# rigidPCB2_rev.net
KiCad netlist of a schematic drawn in Altium Designer
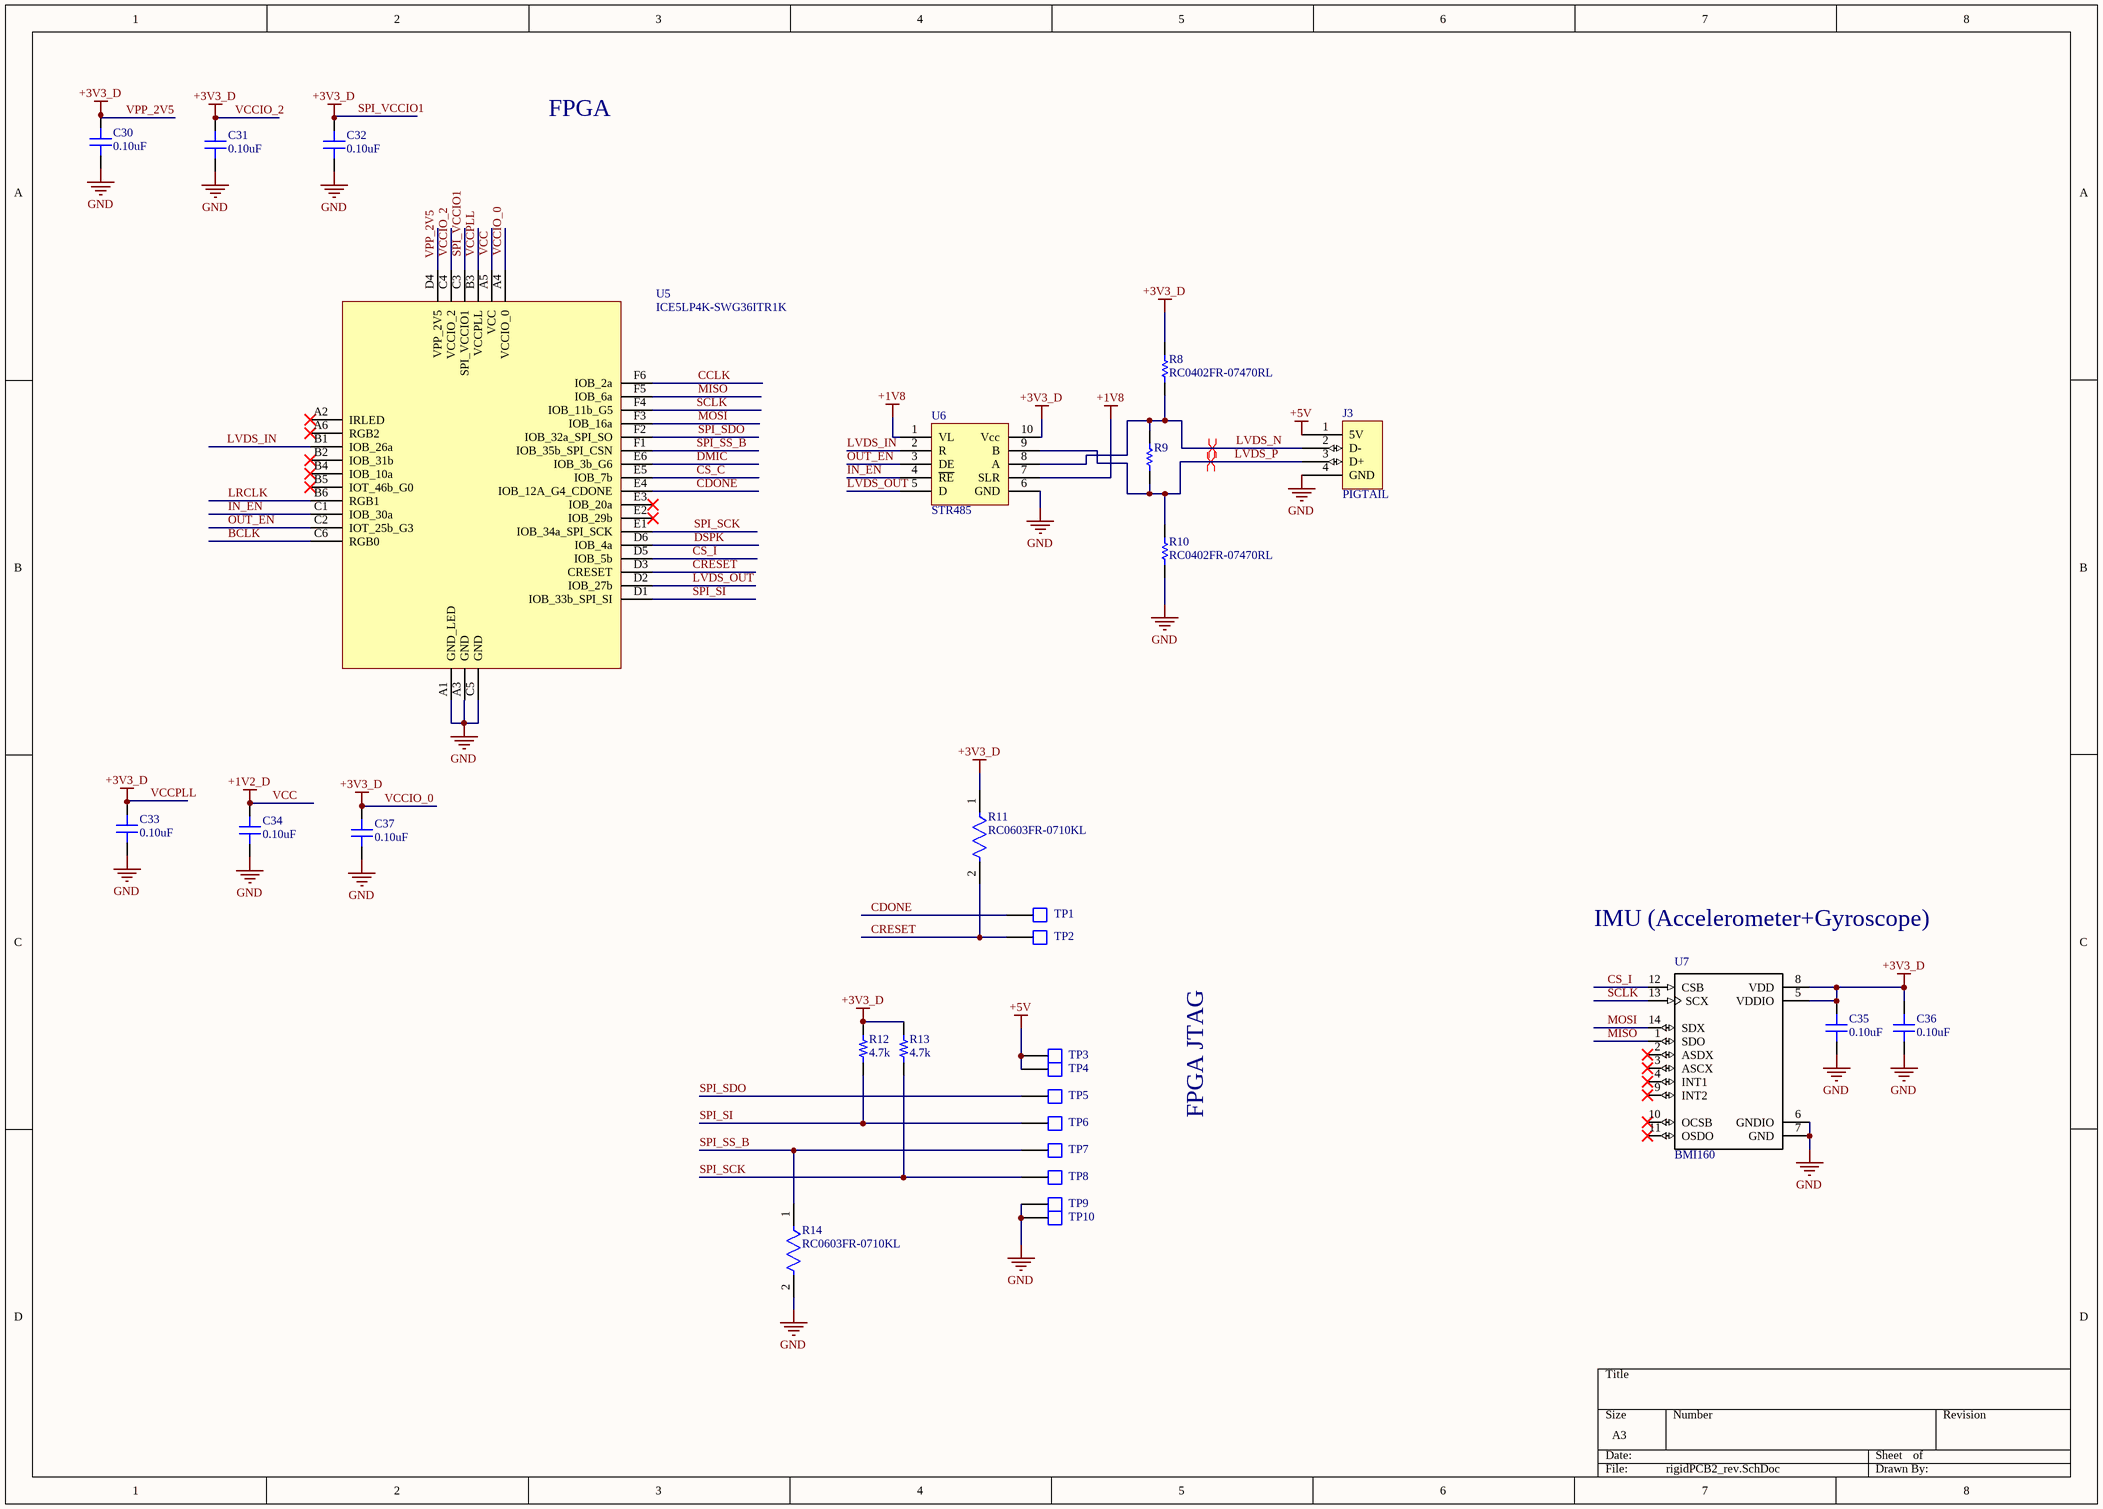
[diagram p0: rigidPCB2_rev.SchDoc]

(export (version "E")
  (design (tool "Eeschema 10.0.6"))
  (components
    (comp (ref "C30")
      (value "0.10uF")
      (footprint "CAP 0201/0603")
      (description "CAP CER 0.1UF 10V X5R 0201")
      (fields
        (field (name "PART NUMBER") "CL03A104KP3NNNC")
        (field (name "MANUFACTURER") "Samsung Electro-Mechanics America, Inc.")
      )
      (libsource (lib "Celestial Library Database") (part "Capacitor"))
    )
    (comp (ref "C31")
      (value "0.10uF")
      (footprint "CAP 0201/0603")
      (description "CAP CER 0.1UF 10V X5R 0201")
      (fields
        (field (name "PART NUMBER") "CL03A104KP3NNNC")
        (field (name "MANUFACTURER") "Samsung Electro-Mechanics America, Inc.")
      )
      (libsource (lib "Celestial Library Database") (part "Capacitor"))
    )
    (comp (ref "C32")
      (value "0.10uF")
      (footprint "CAP 0201/0603")
      (description "CAP CER 0.1UF 10V X5R 0201")
      (fields
        (field (name "PART NUMBER") "CL03A104KP3NNNC")
        (field (name "MANUFACTURER") "Samsung Electro-Mechanics America, Inc.")
      )
      (libsource (lib "Celestial Library Database") (part "Capacitor"))
    )
    (comp (ref "C33")
      (value "0.10uF")
      (footprint "CAP 0201/0603")
      (description "CAP CER 0.1UF 10V X5R 0201")
      (fields
        (field (name "PART NUMBER") "CL03A104KP3NNNC")
        (field (name "MANUFACTURER") "Samsung Electro-Mechanics America, Inc.")
      )
      (libsource (lib "Celestial Library Database") (part "Capacitor"))
    )
    (comp (ref "C34")
      (value "0.10uF")
      (footprint "CAP 0201/0603")
      (description "CAP CER 0.1UF 10V X5R 0201")
      (fields
        (field (name "PART NUMBER") "CL03A104KP3NNNC")
        (field (name "MANUFACTURER") "Samsung Electro-Mechanics America, Inc.")
      )
      (libsource (lib "Celestial Library Database") (part "Capacitor"))
    )
    (comp (ref "C35")
      (value "0.10uF")
      (footprint "CAP 0201/0603")
      (description "CAP CER 0.1UF 10V X5R 0201")
      (fields
        (field (name "PART NUMBER") "CL03A104KP3NNNC")
        (field (name "MANUFACTURER") "Samsung Electro-Mechanics America, Inc.")
      )
      (libsource (lib "Celestial Library Database") (part "Capacitor"))
    )
    (comp (ref "C36")
      (value "0.10uF")
      (footprint "CAP 0201/0603")
      (description "CAP CER 0.1UF 10V X5R 0201")
      (fields
        (field (name "PART NUMBER") "CL03A104KP3NNNC")
        (field (name "MANUFACTURER") "Samsung Electro-Mechanics America, Inc.")
      )
      (libsource (lib "Celestial Library Database") (part "Capacitor"))
    )
    (comp (ref "C37")
      (value "0.10uF")
      (footprint "CAP 0201/0603")
      (description "CAP CER 0.1UF 10V X5R 0201")
      (fields
        (field (name "PART NUMBER") "CL03A104KP3NNNC")
        (field (name "MANUFACTURER") "Samsung Electro-Mechanics America, Inc.")
      )
      (libsource (lib "Celestial Library Database") (part "Capacitor"))
    )
    (comp (ref "J3")
      (value "PIGTAIL")
      (footprint "PIGTAIL")
      (libsource (lib "Mark_Library1") (part "PIGTAIL"))
    )
    (comp (ref "R8")
      (value "RC0402FR-07470RL")
      (footprint "RESC1005X40X25ML05T10")
      (fields (field (name "MANUFACTURER") "Yageo / Phycomp"))
      (libsource (lib "Altium Content Vault") (part "RES"))
    )
    (comp (ref "R9")
      (value "RC0402FR-0745R3L")
      (footprint "RESC1005X40X25ML05T10")
      (fields (field (name "MANUFACTURER") "Yageo / Phycomp"))
      (libsource (lib "Altium Content Vault") (part "RES"))
    )
    (comp (ref "R10")
      (value "RC0402FR-07470RL")
      (footprint "RESC1005X40X25ML05T10")
      (fields (field (name "MANUFACTURER") "Yageo / Phycomp"))
      (libsource (lib "Altium Content Vault") (part "RES"))
    )
    (comp (ref "R11")
      (value "RC0603FR-0710KL")
      (footprint "FP-RC0603-0_55-IPC_C")
      (description "RES 10K OHM 1% 1/10W 0603")
      (fields (field (name "TOLERANCE") "1%"))
      (libsource (lib "Altium Content Vault") (part "1029c3af85768c4190bb7ad29bc67b5"))
    )
    (comp (ref "R12")
      (value "4.7k")
      (footprint "RES 0201/0603")
      (description "RES SMD 4.7K OHM 1% 1/20W 0201")
      (fields (field (name "PART NUMBER") "RC0201FR-074K7L") (field (name "MANUFACTURER") "Yageo"))
      (libsource (lib "Celestial Library Database") (part "Resistor"))
    )
    (comp (ref "R13")
      (value "4.7k")
      (footprint "RES 0201/0603")
      (description "RES SMD 4.7K OHM 1% 1/20W 0201")
      (fields (field (name "PART NUMBER") "RC0201FR-074K7L") (field (name "MANUFACTURER") "Yageo"))
      (libsource (lib "Celestial Library Database") (part "Resistor"))
    )
    (comp (ref "R14")
      (value "RC0603FR-0710KL")
      (footprint "FP-RC0603-0_55-IPC_C")
      (description "RES 10K OHM 1% 1/10W 0603")
      (fields (field (name "TOLERANCE") "1%"))
      (libsource (lib "Altium Content Vault") (part "1029c3af85768c4190bb7ad29bc67b5"))
    )
    (comp (ref "TP1")
      (value "TP_SMD_DJB")
      (footprint "TP_SMD_DJB")
      (description "Digital Jellybean Style SMD Test Point")
      (libsource (lib "OSP_Symbols") (part "TP_SMD_DJB"))
    )
    (comp (ref "TP2")
      (value "TP_SMD_DJB")
      (footprint "TP_SMD_DJB")
      (description "Digital Jellybean Style SMD Test Point")
      (libsource (lib "OSP_Symbols") (part "TP_SMD_DJB"))
    )
    (comp (ref "TP3")
      (value "TP_SMD_DJB")
      (footprint "TP_SMD_DJB")
      (description "Digital Jellybean Style SMD Test Point")
      (libsource (lib "OSP_Symbols") (part "TP_SMD_DJB"))
    )
    (comp (ref "TP4")
      (value "TP_SMD_DJB")
      (footprint "TP_SMD_DJB")
      (description "Digital Jellybean Style SMD Test Point")
      (libsource (lib "OSP_Symbols") (part "TP_SMD_DJB"))
    )
    (comp (ref "TP5")
      (value "TP_SMD_DJB")
      (footprint "TP_SMD_DJB")
      (description "Digital Jellybean Style SMD Test Point")
      (libsource (lib "OSP_Symbols") (part "TP_SMD_DJB"))
    )
    (comp (ref "TP6")
      (value "TP_SMD_DJB")
      (footprint "TP_SMD_DJB")
      (description "Digital Jellybean Style SMD Test Point")
      (libsource (lib "OSP_Symbols") (part "TP_SMD_DJB"))
    )
    (comp (ref "TP7")
      (value "TP_SMD_DJB")
      (footprint "TP_SMD_DJB")
      (description "Digital Jellybean Style SMD Test Point")
      (libsource (lib "OSP_Symbols") (part "TP_SMD_DJB"))
    )
    (comp (ref "TP8")
      (value "TP_SMD_DJB")
      (footprint "TP_SMD_DJB")
      (description "Digital Jellybean Style SMD Test Point")
      (libsource (lib "OSP_Symbols") (part "TP_SMD_DJB"))
    )
    (comp (ref "TP9")
      (value "TP_SMD_DJB")
      (footprint "TP_SMD_DJB")
      (description "Digital Jellybean Style SMD Test Point")
      (libsource (lib "OSP_Symbols") (part "TP_SMD_DJB"))
    )
    (comp (ref "TP10")
      (value "TP_SMD_DJB")
      (footprint "TP_SMD_DJB")
      (description "Digital Jellybean Style SMD Test Point")
      (libsource (lib "OSP_Symbols") (part "TP_SMD_DJB"))
    )
    (comp (ref "U5")
      (value "ICE5LP4K-SWG36ITR1K")
      (footprint "36-XFBGA")
      (description "Field Programmable Gate Array (FPGA) IC 25 65536 1280 36-VFBGA")
      (libsource (lib "OSP_DJB_Rigid") (part "ICE5LP4K-SWG36ITR1K"))
    )
    (comp (ref "U6")
      (value "STR485")
      (footprint "STR485LVQT")
      (description "3.3 V LVDS RS485 compatible with 1.8 V I/Os and selectable speed")
      (libsource (lib "OSP_DJB_Rigid") (part "STR485"))
    )
    (comp (ref "U7")
      (value "BMI160")
      (footprint "LGA14R50P5X4_300X250X83")
      (description "BMI160 2.5 x 3 mm Tiaxial Accelerometer / Gyroscope Inertial Measurement Unit")
      (fields (field (name "MF") "Bosch"))
      (libsource (lib "Mark_Library1") (part "BMI160_1"))
    )
  )
  (nets
    (net (code "1") (name "+1V2_D") (class "Default")
      (node (ref "C34") (pin "2") (pinfunction "2_2") (pintype "passive"))
      (node (ref "U5") (pin "A5") (pinfunction "VCC_A5") (pintype "passive"))
    )
    (net (code "2") (name "+1V8") (class "Default")
      (node (ref "U6") (pin "1") (pinfunction "VL_1") (pintype "passive"))
      (node (ref "U6") (pin "7") (pinfunction "SLR_7") (pintype "passive"))
    )
    (net (code "3") (name "+3V3_D") (class "Default")
      (node (ref "C30") (pin "2") (pinfunction "2_2") (pintype "passive"))
      (node (ref "C31") (pin "2") (pinfunction "2_2") (pintype "passive"))
      (node (ref "C32") (pin "2") (pinfunction "2_2") (pintype "passive"))
      (node (ref "C33") (pin "2") (pinfunction "2_2") (pintype "passive"))
      (node (ref "C35") (pin "2") (pinfunction "2_2") (pintype "passive"))
      (node (ref "C36") (pin "2") (pinfunction "2_2") (pintype "passive"))
      (node (ref "C37") (pin "2") (pinfunction "2_2") (pintype "passive"))
      (node (ref "R11") (pin "1") (pinfunction "1_1") (pintype "passive"))
      (node (ref "R12") (pin "2") (pinfunction "2_2") (pintype "passive"))
      (node (ref "R13") (pin "2") (pinfunction "2_2") (pintype "passive"))
      (node (ref "R8") (pin "2") (pinfunction "2_2") (pintype "passive"))
      (node (ref "U5") (pin "A4") (pinfunction "VCCIO_0_A4") (pintype "passive"))
      (node (ref "U5") (pin "B3") (pinfunction "VCCPLL_B3") (pintype "passive"))
      (node (ref "U5") (pin "C3") (pinfunction "SPI_VCCIO1_C3") (pintype "passive"))
      (node (ref "U5") (pin "C4") (pinfunction "VCCIO_2_C4") (pintype "passive"))
      (node (ref "U5") (pin "D4") (pinfunction "VPP_2V5_D4") (pintype "passive"))
      (node (ref "U6") (pin "10") (pinfunction "Vcc_10") (pintype "passive"))
      (node (ref "U7") (pin "5") (pinfunction "VDDIO_5") (pintype "power_in"))
      (node (ref "U7") (pin "8") (pinfunction "VDD_8") (pintype "power_in"))
    )
    (net (code "4") (name "+5V") (class "Default")
      (node (ref "J3") (pin "1") (pinfunction "5V_1") (pintype "power_in"))
      (node (ref "TP3") (pin "1") (pintype "passive"))
      (node (ref "TP4") (pin "1") (pintype "passive"))
    )
    (net (code "5") (name "/BCLK") (class "Default")
      (node (ref "U5") (pin "C6") (pinfunction "RGB0_C6") (pintype "passive"))
    )
    (net (code "6") (name "/CCLK") (class "Default")
      (node (ref "U5") (pin "F6") (pinfunction "IOB_2a_F6") (pintype "passive"))
    )
    (net (code "7") (name "/CDONE") (class "Default")
      (node (ref "TP1") (pin "1") (pintype "passive"))
      (node (ref "U5") (pin "E4") (pinfunction "IOB_12A_G4_CDONE_E4") (pintype "passive"))
    )
    (net (code "8") (name "/CRESET") (class "Default")
      (node (ref "R11") (pin "2") (pinfunction "2_2") (pintype "passive"))
      (node (ref "TP2") (pin "1") (pintype "passive"))
      (node (ref "U5") (pin "D3") (pinfunction "CRESET_D3") (pintype "passive"))
    )
    (net (code "9") (name "/CS_C") (class "Default")
      (node (ref "U5") (pin "E5") (pinfunction "IOB_7b_E5") (pintype "passive"))
    )
    (net (code "10") (name "/CS_I") (class "Default")
      (node (ref "U5") (pin "D5") (pinfunction "IOB_5b_D5") (pintype "passive"))
      (node (ref "U7") (pin "12") (pinfunction "CSB_12") (pintype "input"))
    )
    (net (code "11") (name "/DMIC") (class "Default")
      (node (ref "U5") (pin "E6") (pinfunction "IOB_3b_G6_E6") (pintype "passive"))
    )
    (net (code "12") (name "/DSPK") (class "Default")
      (node (ref "U5") (pin "D6") (pinfunction "IOB_4a_D6") (pintype "passive"))
    )
    (net (code "13") (name "/IN_EN") (class "Default")
      (node (ref "U5") (pin "C1") (pinfunction "IOB_30a_C1") (pintype "passive"))
      (node (ref "U6") (pin "4") (pinfunction "~{RE}_4") (pintype "passive"))
    )
    (net (code "14") (name "/LRCLK") (class "Default")
      (node (ref "U5") (pin "B6") (pinfunction "RGB1_B6") (pintype "passive"))
    )
    (net (code "15") (name "/LVDS_IN") (class "Default")
      (node (ref "U5") (pin "B1") (pinfunction "IOB_26a_B1") (pintype "passive"))
      (node (ref "U6") (pin "2") (pinfunction "R_2") (pintype "passive"))
    )
    (net (code "16") (name "/LVDS_N") (class "Default")
      (node (ref "J3") (pin "2") (pinfunction "D-_2") (pintype "bidirectional"))
      (node (ref "R8") (pin "1") (pinfunction "1_1") (pintype "passive"))
      (node (ref "R9") (pin "2") (pinfunction "2_2") (pintype "passive"))
      (node (ref "U6") (pin "8") (pinfunction "A_8") (pintype "passive"))
    )
    (net (code "17") (name "/LVDS_OUT") (class "Default")
      (node (ref "U5") (pin "D2") (pinfunction "IOB_27b_D2") (pintype "passive"))
      (node (ref "U6") (pin "5") (pinfunction "D_5") (pintype "passive"))
    )
    (net (code "18") (name "/LVDS_P") (class "Default")
      (node (ref "J3") (pin "3") (pinfunction "D+_3") (pintype "bidirectional"))
      (node (ref "R10") (pin "2") (pinfunction "2_2") (pintype "passive"))
      (node (ref "R9") (pin "1") (pinfunction "1_1") (pintype "passive"))
      (node (ref "U6") (pin "9") (pinfunction "B_9") (pintype "passive"))
    )
    (net (code "19") (name "/MISO") (class "Default")
      (node (ref "U5") (pin "F5") (pinfunction "IOB_6a_F5") (pintype "passive"))
      (node (ref "U7") (pin "1") (pinfunction "SDO_1") (pintype "bidirectional"))
    )
    (net (code "20") (name "/MOSI") (class "Default")
      (node (ref "U5") (pin "F3") (pinfunction "IOB_16a_F3") (pintype "passive"))
      (node (ref "U7") (pin "14") (pinfunction "SDX_14") (pintype "bidirectional"))
    )
    (net (code "21") (name "/OUT_EN") (class "Default")
      (node (ref "U5") (pin "C2") (pinfunction "IOT_25b_G3_C2") (pintype "passive"))
      (node (ref "U6") (pin "3") (pinfunction "DE_3") (pintype "passive"))
    )
    (net (code "22") (name "/SCLK") (class "Default")
      (node (ref "U5") (pin "F4") (pinfunction "IOB_11b_G5_F4") (pintype "passive"))
      (node (ref "U7") (pin "13") (pinfunction "SCX_13") (pintype "input"))
    )
    (net (code "23") (name "/SPI_SCK") (class "Default")
      (node (ref "R13") (pin "1") (pinfunction "1_1") (pintype "passive"))
      (node (ref "TP8") (pin "1") (pintype "passive"))
      (node (ref "U5") (pin "E1") (pinfunction "IOB_34a_SPI_SCK_E1") (pintype "passive"))
    )
    (net (code "24") (name "/SPI_SDO") (class "Default")
      (node (ref "TP5") (pin "1") (pintype "passive"))
      (node (ref "U5") (pin "F2") (pinfunction "IOB_32a_SPI_SO_F2") (pintype "passive"))
    )
    (net (code "25") (name "/SPI_SI") (class "Default")
      (node (ref "R12") (pin "1") (pinfunction "1_1") (pintype "passive"))
      (node (ref "TP6") (pin "1") (pintype "passive"))
      (node (ref "U5") (pin "D1") (pinfunction "IOB_33b_SPI_SI_D1") (pintype "passive"))
    )
    (net (code "26") (name "/SPI_SS_B") (class "Default")
      (node (ref "R14") (pin "1") (pinfunction "1_1") (pintype "passive"))
      (node (ref "TP7") (pin "1") (pintype "passive"))
      (node (ref "U5") (pin "F1") (pinfunction "IOB_35b_SPI_CSN_F1") (pintype "passive"))
    )
    (net (code "27") (name "GND") (class "Default")
      (node (ref "C30") (pin "1") (pinfunction "1_1") (pintype "passive"))
      (node (ref "C31") (pin "1") (pinfunction "1_1") (pintype "passive"))
      (node (ref "C32") (pin "1") (pinfunction "1_1") (pintype "passive"))
      (node (ref "C33") (pin "1") (pinfunction "1_1") (pintype "passive"))
      (node (ref "C34") (pin "1") (pinfunction "1_1") (pintype "passive"))
      (node (ref "C35") (pin "1") (pinfunction "1_1") (pintype "passive"))
      (node (ref "C36") (pin "1") (pinfunction "1_1") (pintype "passive"))
      (node (ref "C37") (pin "1") (pinfunction "1_1") (pintype "passive"))
      (node (ref "J3") (pin "4") (pinfunction "GND_4") (pintype "power_in"))
      (node (ref "R10") (pin "1") (pinfunction "1_1") (pintype "passive"))
      (node (ref "R14") (pin "2") (pinfunction "2_2") (pintype "passive"))
      (node (ref "TP10") (pin "1") (pintype "passive"))
      (node (ref "TP9") (pin "1") (pintype "passive"))
      (node (ref "U5") (pin "A1") (pinfunction "GND_LED_A1") (pintype "passive"))
      (node (ref "U5") (pin "A3") (pinfunction "GND_A3") (pintype "passive"))
      (node (ref "U5") (pin "C5") (pinfunction "GND_C5") (pintype "passive"))
      (node (ref "U6") (pin "6") (pinfunction "GND_6") (pintype "passive"))
      (node (ref "U7") (pin "6") (pinfunction "GNDIO_6") (pintype "power_in"))
      (node (ref "U7") (pin "7") (pinfunction "GND_7") (pintype "power_in"))
    )
    (net (code "28") (name "unconnected-(U5-IOB_10a-PadB4)") (class "Default")
      (node (ref "U5") (pin "B4") (pinfunction "IOB_10a_B4") (pintype "passive+no_connect"))
    )
    (net (code "29") (name "unconnected-(U5-IOB_20a-PadE3)") (class "Default")
      (node (ref "U5") (pin "E3") (pinfunction "IOB_20a_E3") (pintype "passive+no_connect"))
    )
    (net (code "30") (name "unconnected-(U5-IOB_29b-PadE2)") (class "Default")
      (node (ref "U5") (pin "E2") (pinfunction "IOB_29b_E2") (pintype "passive+no_connect"))
    )
    (net (code "31") (name "unconnected-(U5-IOB_31b-PadB2)") (class "Default")
      (node (ref "U5") (pin "B2") (pinfunction "IOB_31b_B2") (pintype "passive+no_connect"))
    )
    (net (code "32") (name "unconnected-(U5-IOT_46b_G0-PadB5)") (class "Default")
      (node (ref "U5") (pin "B5") (pinfunction "IOT_46b_G0_B5") (pintype "passive+no_connect"))
    )
    (net (code "33") (name "unconnected-(U5-IRLED-PadA2)") (class "Default")
      (node (ref "U5") (pin "A2") (pinfunction "IRLED_A2") (pintype "passive+no_connect"))
    )
    (net (code "34") (name "unconnected-(U5-RGB2-PadA6)") (class "Default")
      (node (ref "U5") (pin "A6") (pinfunction "RGB2_A6") (pintype "passive+no_connect"))
    )
    (net (code "35") (name "unconnected-(U7-ASCX-Pad3)") (class "Default")
      (node (ref "U7") (pin "3") (pinfunction "ASCX_3") (pintype "bidirectional+no_connect"))
    )
    (net (code "36") (name "unconnected-(U7-ASDX-Pad2)") (class "Default")
      (node (ref "U7") (pin "2") (pinfunction "ASDX_2") (pintype "bidirectional+no_connect"))
    )
    (net (code "37") (name "unconnected-(U7-INT1-Pad4)") (class "Default")
      (node (ref "U7") (pin "4") (pinfunction "INT1_4") (pintype "bidirectional+no_connect"))
    )
    (net (code "38") (name "unconnected-(U7-INT2-Pad9)") (class "Default")
      (node (ref "U7") (pin "9") (pinfunction "INT2_9") (pintype "bidirectional+no_connect"))
    )
    (net (code "39") (name "unconnected-(U7-OCSB-Pad10)") (class "Default")
      (node (ref "U7") (pin "10") (pinfunction "OCSB_10") (pintype "bidirectional+no_connect"))
    )
    (net (code "40") (name "unconnected-(U7-OSDO-Pad11)") (class "Default")
      (node (ref "U7") (pin "11") (pinfunction "OSDO_11") (pintype "bidirectional+no_connect"))
    )
  )
)
